# EnvFollower.net
KiCad netlist of a schematic drawn in EAGLE
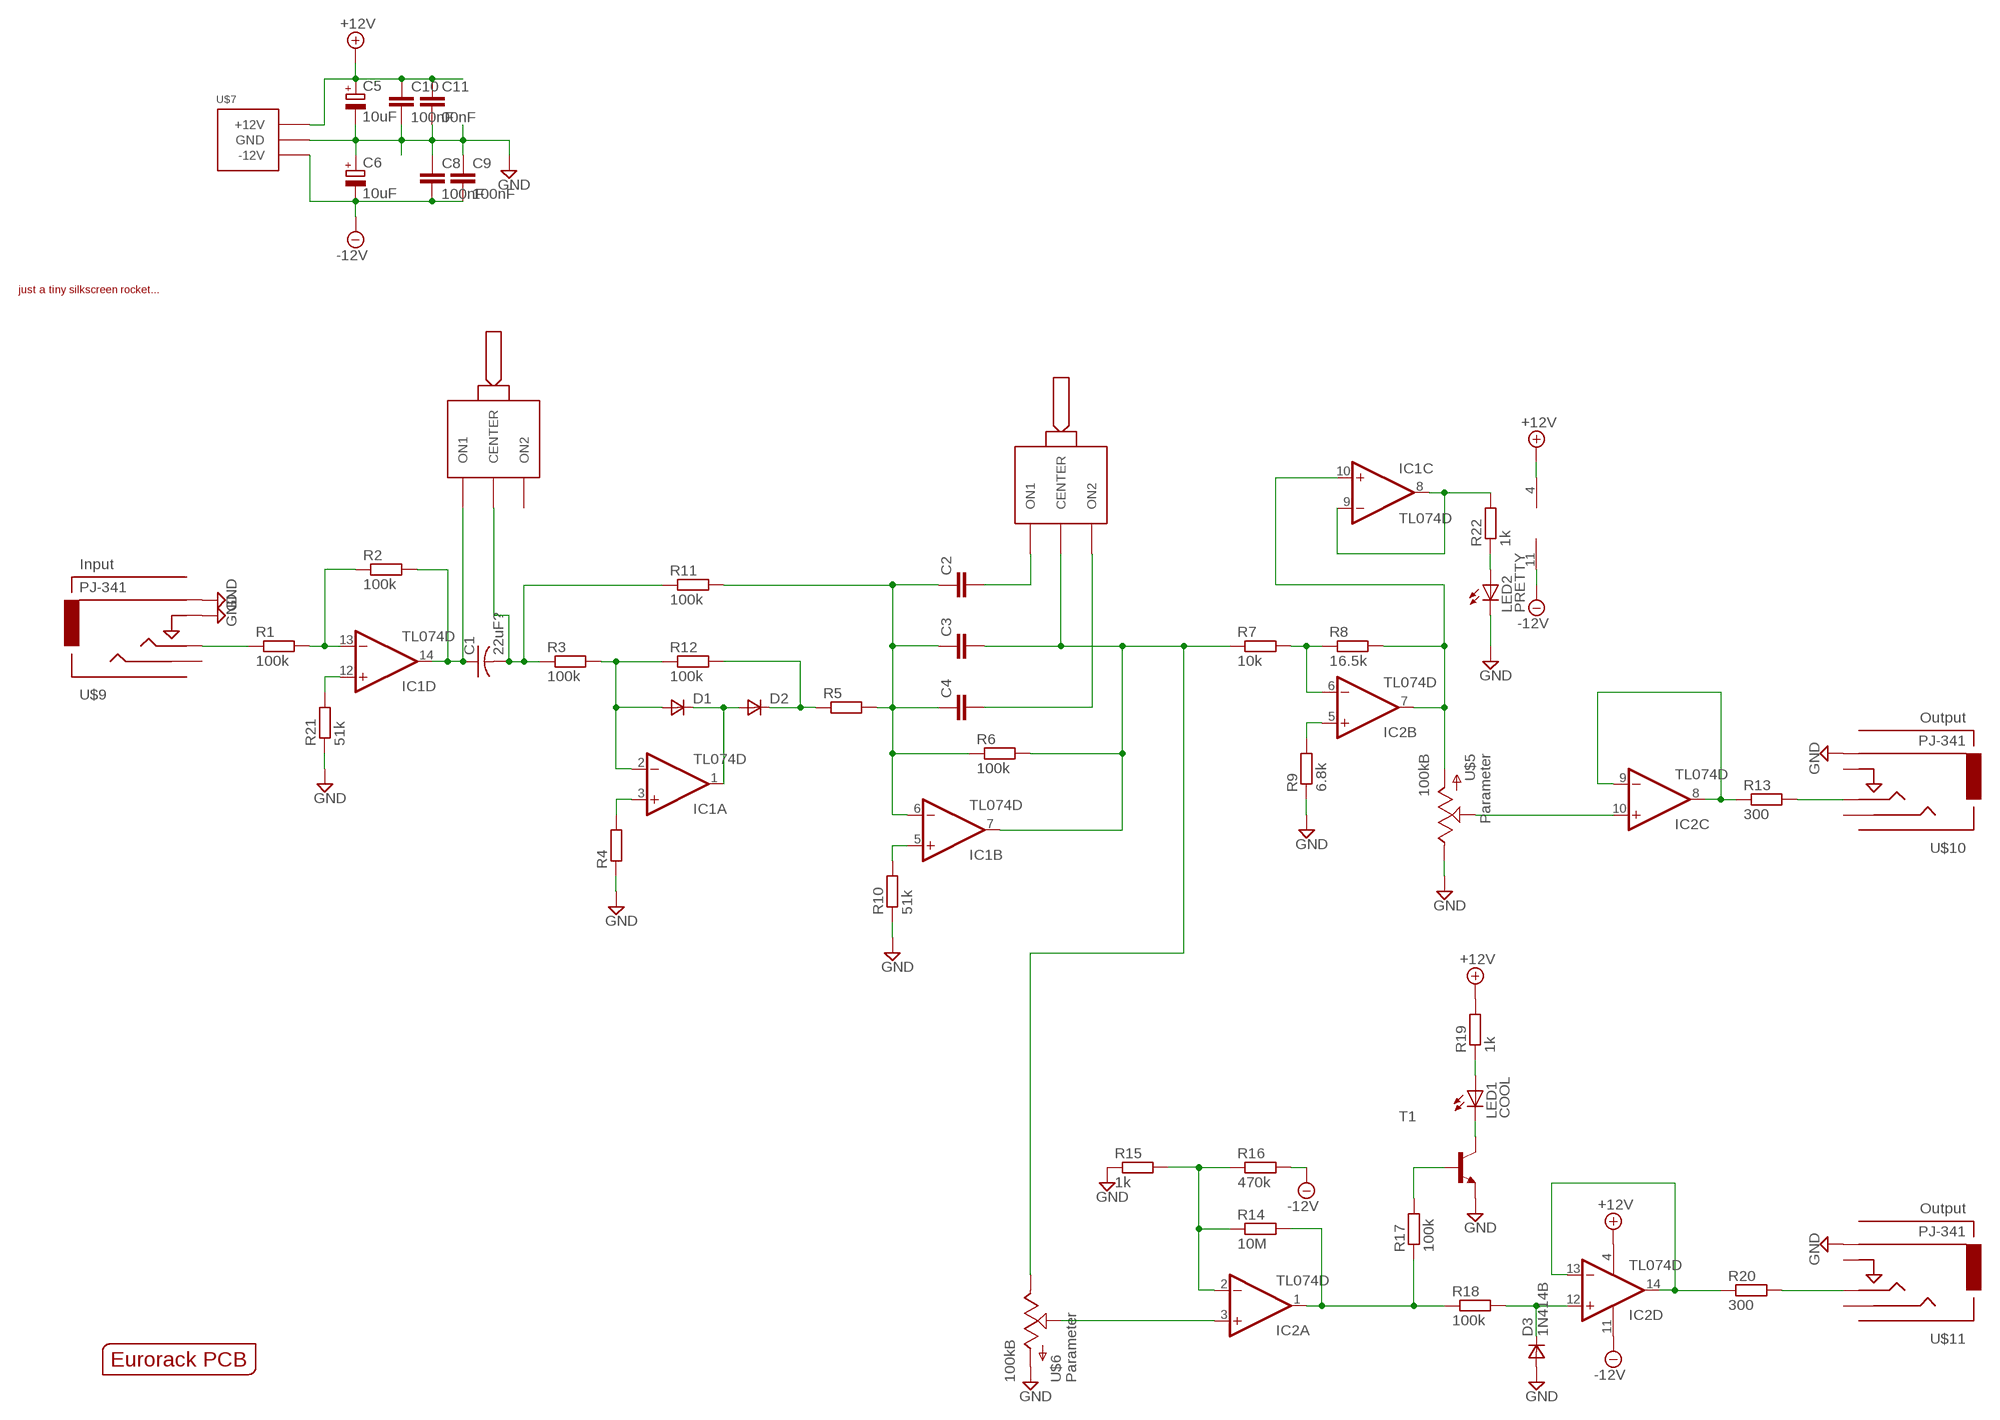
[diagram p0: schematic, sheet 1]

(export (version "E")
  (design (tool "Eeschema 10.0.6"))
  (components
    (comp (ref "C1")
      (value "22uF?")
      (footprint "eagle-import:C1210K")
      (libsource (lib "eagle-import") (part "C-USC1210K"))
    )
    (comp (ref "C2")
      (value "C-EUC0603K")
      (footprint "eagle-import:C0603K")
      (libsource (lib "eagle-import") (part "C-EUC0603K"))
    )
    (comp (ref "C3")
      (value "C-EUC0603K")
      (footprint "eagle-import:C0603K")
      (libsource (lib "eagle-import") (part "C-EUC0603K"))
    )
    (comp (ref "C4")
      (value "C-EUC0603K")
      (footprint "eagle-import:C0603K")
      (libsource (lib "eagle-import") (part "C-EUC0603K"))
    )
    (comp (ref "C5")
      (value "10uF")
      (footprint "eagle-import:153CLV-0505")
      (libsource (lib "eagle-import") (part "CPOL-EU153CLV-0505"))
    )
    (comp (ref "C6")
      (value "10uF")
      (footprint "eagle-import:153CLV-0505")
      (libsource (lib "eagle-import") (part "CPOL-EU153CLV-0505"))
    )
    (comp (ref "C8")
      (value "100nF")
      (footprint "eagle-import:C0603K")
      (libsource (lib "eagle-import") (part "C-EUC0603K"))
    )
    (comp (ref "C9")
      (value "100nF")
      (footprint "eagle-import:C0603K")
      (libsource (lib "eagle-import") (part "C-EUC0603K"))
    )
    (comp (ref "C10")
      (value "100nF")
      (footprint "eagle-import:C0603K")
      (libsource (lib "eagle-import") (part "C-EUC0603K"))
    )
    (comp (ref "C11")
      (value "00nF")
      (footprint "eagle-import:C0603K")
      (libsource (lib "eagle-import") (part "C-EUC0603K"))
    )
    (comp (ref "D1")
      (value "DSOT23")
      (footprint "eagle-import:SOT-23")
      (fields (field (name "MPN") "CDSOT23-T03"))
      (libsource (lib "eagle-import") (part "DSOT23"))
    )
    (comp (ref "D2")
      (value "DSOT23")
      (footprint "eagle-import:SOT-23")
      (fields (field (name "MPN") "CDSOT23-T03"))
      (libsource (lib "eagle-import") (part "DSOT23"))
    )
    (comp (ref "D3")
      (value "1N414B")
      (footprint "eagle-import:SOT-23")
      (fields (field (name "MPN") "CDSOT23-T03"))
      (libsource (lib "eagle-import") (part "DSOT23"))
    )
    (comp (ref "IC1")
      (value "TL074D")
      (footprint "eagle-import:SO14")
      (libsource (lib "eagle-import") (part "TL074D"))
    )
    (comp (ref "IC2")
      (value "TL074D")
      (footprint "eagle-import:SO14")
      (libsource (lib "eagle-import") (part "TL074D"))
    )
    (comp (ref "LED1")
      (value "COOL")
      (footprint "eagle-import:LED3MM")
      (libsource (lib "eagle-import") (part "LED3MM"))
    )
    (comp (ref "LED2")
      (value "PRETTY")
      (footprint "eagle-import:LED3MM")
      (libsource (lib "eagle-import") (part "LED3MM"))
    )
    (comp (ref "R1")
      (value "100k")
      (footprint "eagle-import:R0603")
      (libsource (lib "eagle-import") (part "R-EU_R0603"))
    )
    (comp (ref "R2")
      (value "100k")
      (footprint "eagle-import:R0603")
      (libsource (lib "eagle-import") (part "R-EU_R0603"))
    )
    (comp (ref "R3")
      (value "100k")
      (footprint "eagle-import:R0603")
      (libsource (lib "eagle-import") (part "R-EU_R0603"))
    )
    (comp (ref "R4")
      (value "R-EU_R0603")
      (footprint "eagle-import:R0603")
      (libsource (lib "eagle-import") (part "R-EU_R0603"))
    )
    (comp (ref "R5")
      (value "R-EU_R0603")
      (footprint "eagle-import:R0603")
      (libsource (lib "eagle-import") (part "R-EU_R0603"))
    )
    (comp (ref "R6")
      (value "100k")
      (footprint "eagle-import:R0603")
      (libsource (lib "eagle-import") (part "R-EU_R0603"))
    )
    (comp (ref "R7")
      (value "10k")
      (footprint "eagle-import:R0603")
      (libsource (lib "eagle-import") (part "R-EU_R0603"))
    )
    (comp (ref "R8")
      (value "16.5k")
      (footprint "eagle-import:R0603")
      (libsource (lib "eagle-import") (part "R-EU_R0603"))
    )
    (comp (ref "R9")
      (value "6.8k")
      (footprint "eagle-import:R0603")
      (libsource (lib "eagle-import") (part "R-EU_R0603"))
    )
    (comp (ref "R10")
      (value "51k")
      (footprint "eagle-import:R0603")
      (libsource (lib "eagle-import") (part "R-EU_R0603"))
    )
    (comp (ref "R11")
      (value "100k")
      (footprint "eagle-import:R0603")
      (libsource (lib "eagle-import") (part "R-EU_R0603"))
    )
    (comp (ref "R12")
      (value "100k")
      (footprint "eagle-import:R0603")
      (libsource (lib "eagle-import") (part "R-EU_R0603"))
    )
    (comp (ref "R13")
      (value "300")
      (footprint "eagle-import:R0603")
      (libsource (lib "eagle-import") (part "R-EU_R0603"))
    )
    (comp (ref "R14")
      (value "10M")
      (footprint "eagle-import:R0603")
      (libsource (lib "eagle-import") (part "R-EU_R0603"))
    )
    (comp (ref "R15")
      (value "1k")
      (footprint "eagle-import:R0603")
      (libsource (lib "eagle-import") (part "R-EU_R0603"))
    )
    (comp (ref "R16")
      (value "470k")
      (footprint "eagle-import:R0603")
      (libsource (lib "eagle-import") (part "R-EU_R0603"))
    )
    (comp (ref "R17")
      (value "100k")
      (footprint "eagle-import:R0603")
      (libsource (lib "eagle-import") (part "R-EU_R0603"))
    )
    (comp (ref "R18")
      (value "100k")
      (footprint "eagle-import:R0603")
      (libsource (lib "eagle-import") (part "R-EU_R0603"))
    )
    (comp (ref "R19")
      (value "1k")
      (footprint "eagle-import:R0603")
      (libsource (lib "eagle-import") (part "R-EU_R0603"))
    )
    (comp (ref "R20")
      (value "300")
      (footprint "eagle-import:R0603")
      (libsource (lib "eagle-import") (part "R-EU_R0603"))
    )
    (comp (ref "R21")
      (value "51k")
      (footprint "eagle-import:R0603")
      (libsource (lib "eagle-import") (part "R-EU_R0603"))
    )
    (comp (ref "R22")
      (value "1k")
      (footprint "eagle-import:R0603")
      (libsource (lib "eagle-import") (part "R-EU_R0603"))
    )
    (comp (ref "T1")
      (value "BCX70-NPN-SOT23-BEC")
      (footprint "eagle-import:SOT23-BEC")
      (libsource (lib "eagle-import") (part "-NPN-SOT23-BECBCX70"))
    )
    (comp (ref "U$1")
      (value "EURORACK_PCB4HP")
      (footprint "eagle-import:EURORACK4HPPCB")
      (libsource (lib "eagle-import") (part "EURORACK_PCB4HP"))
    )
    (comp (ref "U$2")
      (value "JUSTATINYROCKET")
      (footprint "eagle-import:JUSTATINYROCKET")
      (libsource (lib "eagle-import") (part "JUSTATINYROCKET"))
    )
    (comp (ref "U$4")
      (value "ONOFFON")
      (footprint "eagle-import:MULTICOMP1MS-ONOFFON")
      (libsource (lib "eagle-import") (part "ONOFFON"))
    )
    (comp (ref "U$5")
      (value "100kB")
      (footprint "eagle-import:OG-POTS_ALPS_POT_VERTICAL")
      (libsource (lib "eagle-import") (part "POTZEPHPOT"))
    )
    (comp (ref "U$6")
      (value "100kB")
      (footprint "eagle-import:OG-POTS_ALPS_POT_VERTICAL")
      (libsource (lib "eagle-import") (part "POTZEPHPOT"))
    )
    (comp (ref "U$7")
      (value "POWER_SIMPLE10-OTHERSIDE")
      (footprint "eagle-import:POWER_10_LABELSOTHERSIDE")
      (libsource (lib "eagle-import") (part "POWER_SIMPLE10-OTHERSIDE"))
    )
    (comp (ref "U$8")
      (value "ONOFFON")
      (footprint "eagle-import:MULTICOMP1MS-ONOFFON")
      (libsource (lib "eagle-import") (part "ONOFFON"))
    )
    (comp (ref "U$9")
      (value "PJ-341")
      (footprint "eagle-import:3.5MM-JACK-SWITCH-13MM-INPUT")
      (libsource (lib "eagle-import") (part "AUDIO-JACKINPUT"))
    )
    (comp (ref "U$10")
      (value "PJ-341")
      (footprint "eagle-import:3.5MM-JACK-SWITCH-13MM-OUTPUT")
      (libsource (lib "eagle-import") (part "AUDIO-JACKOUTPUT"))
    )
    (comp (ref "U$11")
      (value "PJ-341")
      (footprint "eagle-import:3.5MM-JACK-SWITCH-13MM-OUTPUT")
      (libsource (lib "eagle-import") (part "AUDIO-JACKOUTPUT"))
    )
  )
  (nets
    (net (code "1") (name "+12V") (class "Default")
      (node (ref "C10") (pin "1") (pinfunction "1_1") (pintype "passive"))
      (node (ref "C11") (pin "1") (pinfunction "1_1") (pintype "passive"))
      (node (ref "C5") (pin "+") (pinfunction "+_+") (pintype "passive"))
      (node (ref "IC1") (pin "4") (pinfunction "V+_4") (pintype "power_in"))
      (node (ref "IC2") (pin "4") (pinfunction "V+_4") (pintype "power_in"))
      (node (ref "R19") (pin "2") (pinfunction "2_2") (pintype "passive"))
      (node (ref "U$7") (pin "10") (pinfunction "+12V_10") (pintype "bidirectional"))
      (node (ref "U$7") (pin "9") (pinfunction "+12V_9") (pintype "bidirectional"))
    )
    (net (code "2") (name "-12V") (class "Default")
      (node (ref "C6") (pin "-") (pinfunction "-_-") (pintype "passive"))
      (node (ref "C8") (pin "2") (pinfunction "2_2") (pintype "passive"))
      (node (ref "C9") (pin "2") (pinfunction "2_2") (pintype "passive"))
      (node (ref "IC1") (pin "11") (pinfunction "V-_11") (pintype "power_in"))
      (node (ref "IC2") (pin "11") (pinfunction "V-_11") (pintype "power_in"))
      (node (ref "R16") (pin "2") (pinfunction "2_2") (pintype "passive"))
      (node (ref "U$7") (pin "1") (pinfunction "-12V_1") (pintype "bidirectional"))
      (node (ref "U$7") (pin "2") (pinfunction "-12V_2") (pintype "bidirectional"))
    )
    (net (code "3") (name "GND") (class "Default")
      (node (ref "C10") (pin "2") (pinfunction "2_2") (pintype "passive"))
      (node (ref "C11") (pin "2") (pinfunction "2_2") (pintype "passive"))
      (node (ref "C5") (pin "-") (pinfunction "-_-") (pintype "passive"))
      (node (ref "C6") (pin "+") (pinfunction "+_+") (pintype "passive"))
      (node (ref "C8") (pin "1") (pinfunction "1_1") (pintype "passive"))
      (node (ref "C9") (pin "1") (pinfunction "1_1") (pintype "passive"))
      (node (ref "D3") (pin "3") (pinfunction "A_3") (pintype "passive"))
      (node (ref "LED2") (pin "K") (pinfunction "C_K") (pintype "passive"))
      (node (ref "R10") (pin "1") (pinfunction "1_1") (pintype "passive"))
      (node (ref "R15") (pin "1") (pinfunction "1_1") (pintype "passive"))
      (node (ref "R21") (pin "1") (pinfunction "1_1") (pintype "passive"))
      (node (ref "R4") (pin "1") (pinfunction "1_1") (pintype "passive"))
      (node (ref "R9") (pin "1") (pinfunction "1_1") (pintype "passive"))
      (node (ref "T1") (pin "E") (pinfunction "E_E") (pintype "passive"))
      (node (ref "U$10") (pin "RING@3") (pinfunction "RING_RING@3") (pintype "bidirectional"))
      (node (ref "U$11") (pin "RING@3") (pinfunction "RING_RING@3") (pintype "bidirectional"))
      (node (ref "U$5") (pin "P$1") (pinfunction "E_P$1") (pintype "passive"))
      (node (ref "U$6") (pin "P$3") (pinfunction "A_P$3") (pintype "passive"))
      (node (ref "U$7") (pin "3") (pinfunction "GND_3") (pintype "bidirectional"))
      (node (ref "U$7") (pin "4") (pinfunction "GND_4") (pintype "bidirectional"))
      (node (ref "U$7") (pin "5") (pinfunction "GND_5") (pintype "bidirectional"))
      (node (ref "U$7") (pin "6") (pinfunction "GND_6") (pintype "bidirectional"))
      (node (ref "U$7") (pin "7") (pinfunction "GND_7") (pintype "bidirectional"))
      (node (ref "U$7") (pin "8") (pinfunction "GND_8") (pintype "bidirectional"))
      (node (ref "U$9") (pin "RING@3") (pinfunction "RING_RING@3") (pintype "bidirectional"))
      (node (ref "U$9") (pin "SWITCH@3") (pinfunction "SWITCH_SWITCH@3") (pintype "bidirectional"))
    )
    (net (code "4") (name "Net-(D1-A)") (class "Default")
      (node (ref "D1") (pin "3") (pinfunction "A_3") (pintype "passive"))
      (node (ref "IC1") (pin "2") (pinfunction "-IN_2") (pintype "input"))
      (node (ref "R12") (pin "1") (pinfunction "1_1") (pintype "passive"))
      (node (ref "R3") (pin "2") (pinfunction "2_2") (pintype "passive"))
    )
    (net (code "5") (name "Net-(D1-C)") (class "Default")
      (node (ref "D1") (pin "1") (pinfunction "C_1") (pintype "passive"))
      (node (ref "D2") (pin "3") (pinfunction "A_3") (pintype "passive"))
      (node (ref "IC1") (pin "1") (pinfunction "OUT_1") (pintype "output"))
    )
    (net (code "6") (name "Net-(D2-C)") (class "Default")
      (node (ref "D2") (pin "1") (pinfunction "C_1") (pintype "passive"))
      (node (ref "R12") (pin "2") (pinfunction "2_2") (pintype "passive"))
      (node (ref "R5") (pin "1") (pinfunction "1_1") (pintype "passive"))
    )
    (net (code "7") (name "Net-(D3-C)") (class "Default")
      (node (ref "D3") (pin "1") (pinfunction "C_1") (pintype "passive"))
      (node (ref "IC2") (pin "12") (pinfunction "+IN_12") (pintype "input"))
      (node (ref "R18") (pin "2") (pinfunction "2_2") (pintype "passive"))
    )
    (net (code "8") (name "Net-(IC1A-+IN)") (class "Default")
      (node (ref "IC1") (pin "3") (pinfunction "+IN_3") (pintype "input"))
      (node (ref "R4") (pin "2") (pinfunction "2_2") (pintype "passive"))
    )
    (net (code "9") (name "Net-(IC1B-+IN)") (class "Default")
      (node (ref "IC1") (pin "5") (pinfunction "+IN_5") (pintype "input"))
      (node (ref "R10") (pin "2") (pinfunction "2_2") (pintype "passive"))
    )
    (net (code "10") (name "Net-(IC1B--IN)") (class "Default")
      (node (ref "C2") (pin "1") (pinfunction "1_1") (pintype "passive"))
      (node (ref "C3") (pin "1") (pinfunction "1_1") (pintype "passive"))
      (node (ref "C4") (pin "1") (pinfunction "1_1") (pintype "passive"))
      (node (ref "IC1") (pin "6") (pinfunction "-IN_6") (pintype "input"))
      (node (ref "R11") (pin "2") (pinfunction "2_2") (pintype "passive"))
      (node (ref "R5") (pin "2") (pinfunction "2_2") (pintype "passive"))
      (node (ref "R6") (pin "1") (pinfunction "1_1") (pintype "passive"))
    )
    (net (code "11") (name "Net-(IC1B-OUT)") (class "Default")
      (node (ref "C3") (pin "2") (pinfunction "2_2") (pintype "passive"))
      (node (ref "IC1") (pin "7") (pinfunction "OUT_7") (pintype "output"))
      (node (ref "R6") (pin "2") (pinfunction "2_2") (pintype "passive"))
      (node (ref "R7") (pin "1") (pinfunction "1_1") (pintype "passive"))
      (node (ref "U$6") (pin "P$1") (pinfunction "E_P$1") (pintype "passive"))
      (node (ref "U$8") (pin "2") (pinfunction "CENTER_2") (pintype "bidirectional"))
    )
    (net (code "12") (name "Net-(IC1C-+IN)") (class "Default")
      (node (ref "IC1") (pin "10") (pinfunction "+IN_10") (pintype "input"))
      (node (ref "IC2") (pin "7") (pinfunction "OUT_7") (pintype "output"))
      (node (ref "R8") (pin "2") (pinfunction "2_2") (pintype "passive"))
      (node (ref "U$5") (pin "P$3") (pinfunction "A_P$3") (pintype "passive"))
    )
    (net (code "13") (name "Net-(IC1C--IN)") (class "Default")
      (node (ref "IC1") (pin "8") (pinfunction "OUT_8") (pintype "output"))
      (node (ref "IC1") (pin "9") (pinfunction "-IN_9") (pintype "input"))
      (node (ref "R22") (pin "2") (pinfunction "2_2") (pintype "passive"))
    )
    (net (code "14") (name "Net-(IC1D-+IN)") (class "Default")
      (node (ref "IC1") (pin "12") (pinfunction "+IN_12") (pintype "input"))
      (node (ref "R21") (pin "2") (pinfunction "2_2") (pintype "passive"))
    )
    (net (code "15") (name "Net-(IC1D--IN)") (class "Default")
      (node (ref "IC1") (pin "13") (pinfunction "-IN_13") (pintype "input"))
      (node (ref "R1") (pin "2") (pinfunction "2_2") (pintype "passive"))
      (node (ref "R2") (pin "1") (pinfunction "1_1") (pintype "passive"))
    )
    (net (code "16") (name "Net-(IC1D-OUT)") (class "Default")
      (node (ref "C1") (pin "1") (pinfunction "1_1") (pintype "passive"))
      (node (ref "IC1") (pin "14") (pinfunction "OUT_14") (pintype "output"))
      (node (ref "R2") (pin "2") (pinfunction "2_2") (pintype "passive"))
      (node (ref "U$4") (pin "1") (pinfunction "ON1_1") (pintype "bidirectional"))
    )
    (net (code "17") (name "Net-(IC2A-+IN)") (class "Default")
      (node (ref "IC2") (pin "3") (pinfunction "+IN_3") (pintype "input"))
      (node (ref "U$6") (pin "P$2") (pinfunction "S_P$2") (pintype "passive"))
    )
    (net (code "18") (name "Net-(IC2A--IN)") (class "Default")
      (node (ref "IC2") (pin "2") (pinfunction "-IN_2") (pintype "input"))
      (node (ref "R14") (pin "1") (pinfunction "1_1") (pintype "passive"))
      (node (ref "R15") (pin "2") (pinfunction "2_2") (pintype "passive"))
      (node (ref "R16") (pin "1") (pinfunction "1_1") (pintype "passive"))
    )
    (net (code "19") (name "Net-(IC2A-OUT)") (class "Default")
      (node (ref "IC2") (pin "1") (pinfunction "OUT_1") (pintype "output"))
      (node (ref "R14") (pin "2") (pinfunction "2_2") (pintype "passive"))
      (node (ref "R17") (pin "1") (pinfunction "1_1") (pintype "passive"))
      (node (ref "R18") (pin "1") (pinfunction "1_1") (pintype "passive"))
    )
    (net (code "20") (name "Net-(IC2B-+IN)") (class "Default")
      (node (ref "IC2") (pin "5") (pinfunction "+IN_5") (pintype "input"))
      (node (ref "R9") (pin "2") (pinfunction "2_2") (pintype "passive"))
    )
    (net (code "21") (name "Net-(IC2B--IN)") (class "Default")
      (node (ref "IC2") (pin "6") (pinfunction "-IN_6") (pintype "input"))
      (node (ref "R7") (pin "2") (pinfunction "2_2") (pintype "passive"))
      (node (ref "R8") (pin "1") (pinfunction "1_1") (pintype "passive"))
    )
    (net (code "22") (name "Net-(IC2C-+IN)") (class "Default")
      (node (ref "IC2") (pin "10") (pinfunction "+IN_10") (pintype "input"))
      (node (ref "U$5") (pin "P$2") (pinfunction "S_P$2") (pintype "passive"))
    )
    (net (code "23") (name "Net-(IC2C--IN)") (class "Default")
      (node (ref "IC2") (pin "8") (pinfunction "OUT_8") (pintype "output"))
      (node (ref "IC2") (pin "9") (pinfunction "-IN_9") (pintype "input"))
      (node (ref "R13") (pin "1") (pinfunction "1_1") (pintype "passive"))
    )
    (net (code "24") (name "Net-(IC2D--IN)") (class "Default")
      (node (ref "IC2") (pin "13") (pinfunction "-IN_13") (pintype "input"))
      (node (ref "IC2") (pin "14") (pinfunction "OUT_14") (pintype "output"))
      (node (ref "R20") (pin "1") (pinfunction "1_1") (pintype "passive"))
    )
    (net (code "25") (name "Net-(LED1-C)") (class "Default")
      (node (ref "LED1") (pin "K") (pinfunction "C_K") (pintype "passive"))
      (node (ref "T1") (pin "C") (pinfunction "C_C") (pintype "passive"))
    )
    (net (code "26") (name "Net-(LED1-PadA)") (class "Default")
      (node (ref "LED1") (pin "A") (pinfunction "A_A") (pintype "passive"))
      (node (ref "R19") (pin "1") (pinfunction "1_1") (pintype "passive"))
    )
    (net (code "27") (name "Net-(LED2-PadA)") (class "Default")
      (node (ref "LED2") (pin "A") (pinfunction "A_A") (pintype "passive"))
      (node (ref "R22") (pin "1") (pinfunction "1_1") (pintype "passive"))
    )
    (net (code "28") (name "Net-(R17-Pad2)") (class "Default")
      (node (ref "R17") (pin "2") (pinfunction "2_2") (pintype "passive"))
      (node (ref "T1") (pin "B") (pinfunction "B_B") (pintype "passive"))
    )
    (net (code "29") (name "Net-(U$4-CENTER)") (class "Default")
      (node (ref "C1") (pin "2") (pinfunction "2_2") (pintype "passive"))
      (node (ref "R11") (pin "1") (pinfunction "1_1") (pintype "passive"))
      (node (ref "R3") (pin "1") (pinfunction "1_1") (pintype "passive"))
      (node (ref "U$4") (pin "2") (pinfunction "CENTER_2") (pintype "bidirectional"))
    )
    (net (code "30") (name "Net-(U$8-ON1)") (class "Default")
      (node (ref "C2") (pin "2") (pinfunction "2_2") (pintype "passive"))
      (node (ref "U$8") (pin "1") (pinfunction "ON1_1") (pintype "bidirectional"))
    )
    (net (code "31") (name "Net-(U$8-ON2)") (class "Default")
      (node (ref "C4") (pin "2") (pinfunction "2_2") (pintype "passive"))
      (node (ref "U$8") (pin "3") (pinfunction "ON2_3") (pintype "bidirectional"))
    )
    (net (code "32") (name "Net-(U$9-TIP)") (class "Default")
      (node (ref "R1") (pin "1") (pinfunction "1_1") (pintype "passive"))
      (node (ref "U$9") (pin "TIP@3") (pinfunction "TIP_TIP@3") (pintype "bidirectional"))
    )
    (net (code "33") (name "Net-(U$10-TIP)") (class "Default")
      (node (ref "R13") (pin "2") (pinfunction "2_2") (pintype "passive"))
      (node (ref "U$10") (pin "TIP@3") (pinfunction "TIP_TIP@3") (pintype "bidirectional"))
    )
    (net (code "34") (name "Net-(U$11-TIP)") (class "Default")
      (node (ref "R20") (pin "2") (pinfunction "2_2") (pintype "passive"))
      (node (ref "U$11") (pin "TIP@3") (pinfunction "TIP_TIP@3") (pintype "bidirectional"))
    )
    (net (code "35") (name "unconnected-(U$4-ON2-Pad3)") (class "Default")
      (node (ref "U$4") (pin "3") (pinfunction "ON2_3") (pintype "bidirectional"))
    )
    (net (code "36") (name "unconnected-(U$9-SECOND-PadSECOND@3)") (class "Default")
      (node (ref "U$9") (pin "SECOND@3") (pinfunction "SECOND_SECOND@3") (pintype "bidirectional"))
    )
    (net (code "37") (name "unconnected-(U$10-SECOND-PadSECOND@3)") (class "Default")
      (node (ref "U$10") (pin "SECOND@3") (pinfunction "SECOND_SECOND@3") (pintype "bidirectional"))
    )
    (net (code "38") (name "unconnected-(U$10-SWITCH-PadSWITCH@3)") (class "Default")
      (node (ref "U$10") (pin "SWITCH@3") (pinfunction "SWITCH_SWITCH@3") (pintype "bidirectional"))
    )
    (net (code "39") (name "unconnected-(U$11-SECOND-PadSECOND@3)") (class "Default")
      (node (ref "U$11") (pin "SECOND@3") (pinfunction "SECOND_SECOND@3") (pintype "bidirectional"))
    )
    (net (code "40") (name "unconnected-(U$11-SWITCH-PadSWITCH@3)") (class "Default")
      (node (ref "U$11") (pin "SWITCH@3") (pinfunction "SWITCH_SWITCH@3") (pintype "bidirectional"))
    )
  )
)
